# lightplay2.net
KiCad netlist of a schematic drawn in EAGLE
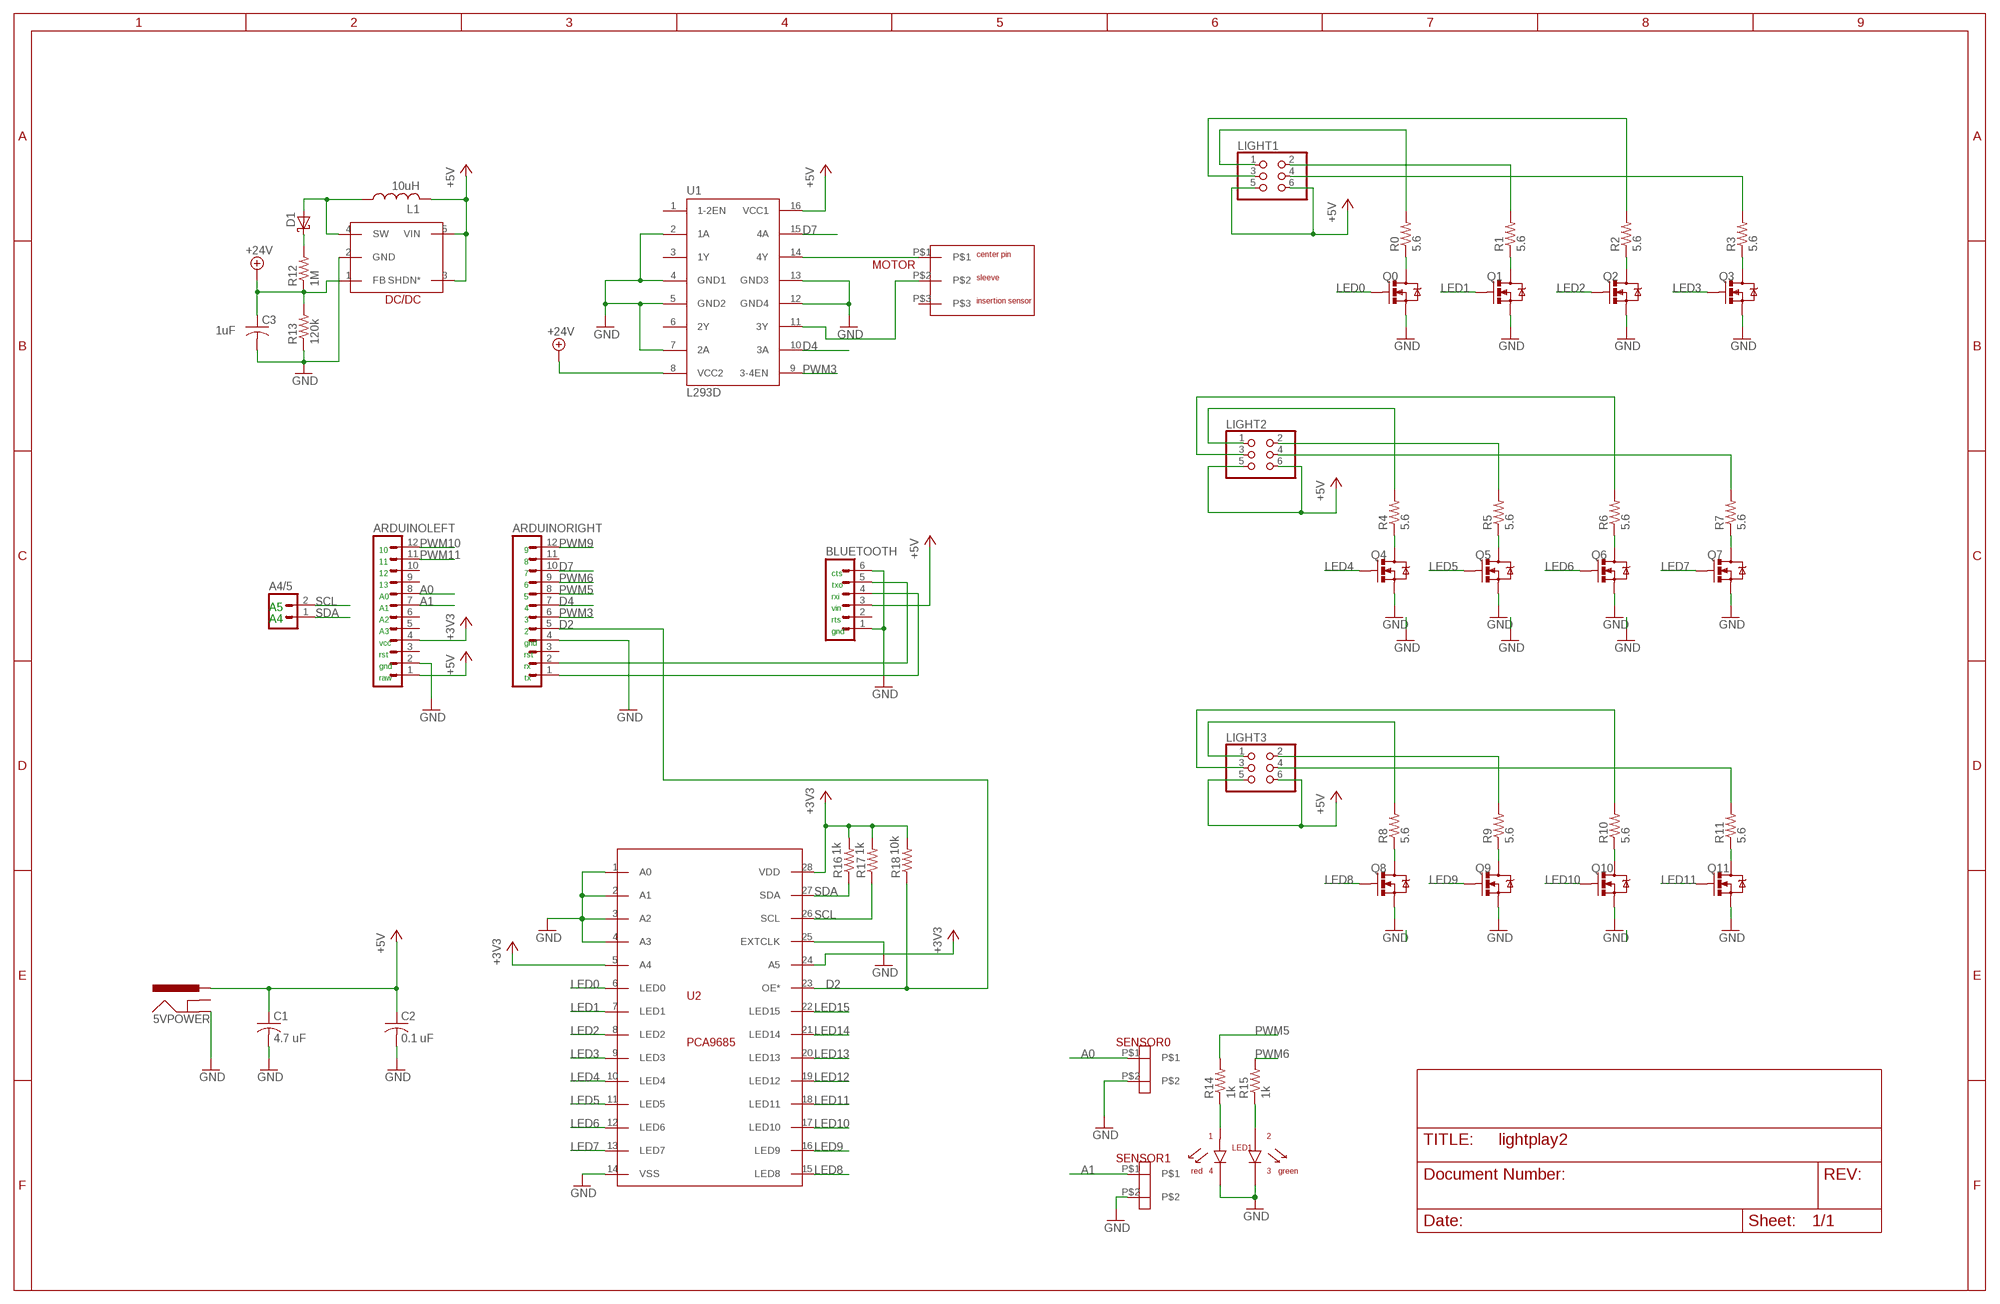
[diagram p0: schematic, sheet 1]

(export (version "E")
  (design (tool "Eeschema 10.0.6"))
  (components
    (comp (ref "5VPOWER")
      (value "POWER_JACKPTH")
      (footprint "eagle-import:POWER_JACK_PTH")
      (libsource (lib "eagle-import") (part "POWER_JACKPTH"))
    )
    (comp (ref "A4/5")
      (value "M02PTH")
      (footprint "eagle-import:1X02")
      (libsource (lib "eagle-import") (part "M02PTH"))
    )
    (comp (ref "ARDUINOLEFT")
      (value "M12PTH")
      (footprint "eagle-import:1X12")
      (libsource (lib "eagle-import") (part "M12PTH"))
    )
    (comp (ref "ARDUINORIGHT")
      (value "M12PTH")
      (footprint "eagle-import:1X12")
      (libsource (lib "eagle-import") (part "M12PTH"))
    )
    (comp (ref "BLUETOOTH")
      (value "M06SILK_FEMALE_PTH")
      (footprint "eagle-import:1X06")
      (libsource (lib "eagle-import") (part "M06SILK_FEMALE_PTH"))
    )
    (comp (ref "C1")
      (value "4.7 uF")
      (footprint "eagle-import:C1206")
      (libsource (lib "eagle-import") (part "C-USC1206"))
    )
    (comp (ref "C2")
      (value "0.1 uF")
      (footprint "eagle-import:C1206")
      (libsource (lib "eagle-import") (part "C-USC1206"))
    )
    (comp (ref "C3")
      (value "1uF")
      (footprint "eagle-import:C1206")
      (libsource (lib "eagle-import") (part "C-USC1206"))
    )
    (comp (ref "D1")
      (value "B120_SHOTTKY_DIODE")
      (footprint "eagle-import:DO214AC")
      (libsource (lib "eagle-import") (part "B120_SHOTTKY_DIODE"))
    )
    (comp (ref "DC/DC")
      (value "LT1615")
      (footprint "eagle-import:SOT23-5")
      (libsource (lib "eagle-import") (part "LT1615"))
    )
    (comp (ref "L1")
      (value "10uH")
      (footprint "eagle-import:INDUCTOR_WURTH")
      (libsource (lib "eagle-import") (part "INDUCTOR_WURTH"))
    )
    (comp (ref "LED1")
      (value "BICOLOR_LED")
      (footprint "eagle-import:BICOLOR_LED")
      (libsource (lib "eagle-import") (part "BICOLOR_LED"))
    )
    (comp (ref "LIGHT1")
      (value "PINHD-2X3")
      (footprint "eagle-import:2X03")
      (libsource (lib "eagle-import") (part "PINHD-2X3"))
    )
    (comp (ref "LIGHT2")
      (value "PINHD-2X3")
      (footprint "eagle-import:2X03")
      (libsource (lib "eagle-import") (part "PINHD-2X3"))
    )
    (comp (ref "LIGHT3")
      (value "PINHD-2X3")
      (footprint "eagle-import:2X03")
      (libsource (lib "eagle-import") (part "PINHD-2X3"))
    )
    (comp (ref "MOTOR")
      (value "PJ-075DH-SMT-TR")
      (footprint "eagle-import:PJ-075DH-SMT-TR")
      (libsource (lib "eagle-import") (part "PJ-075DH-SMT-TR"))
    )
    (comp (ref "Q0")
      (value "MOSFET-NCHANNELAO3404A")
      (footprint "eagle-import:SOT23-3")
      (libsource (lib "eagle-import") (part "MOSFET-NCHANNELAO3404A"))
    )
    (comp (ref "Q1")
      (value "MOSFET-NCHANNELAO3404A")
      (footprint "eagle-import:SOT23-3")
      (libsource (lib "eagle-import") (part "MOSFET-NCHANNELAO3404A"))
    )
    (comp (ref "Q2")
      (value "MOSFET-NCHANNELAO3404A")
      (footprint "eagle-import:SOT23-3")
      (libsource (lib "eagle-import") (part "MOSFET-NCHANNELAO3404A"))
    )
    (comp (ref "Q3")
      (value "MOSFET-NCHANNELAO3404A")
      (footprint "eagle-import:SOT23-3")
      (libsource (lib "eagle-import") (part "MOSFET-NCHANNELAO3404A"))
    )
    (comp (ref "Q4")
      (value "MOSFET-NCHANNELAO3404A")
      (footprint "eagle-import:SOT23-3")
      (libsource (lib "eagle-import") (part "MOSFET-NCHANNELAO3404A"))
    )
    (comp (ref "Q5")
      (value "MOSFET-NCHANNELAO3404A")
      (footprint "eagle-import:SOT23-3")
      (libsource (lib "eagle-import") (part "MOSFET-NCHANNELAO3404A"))
    )
    (comp (ref "Q6")
      (value "MOSFET-NCHANNELAO3404A")
      (footprint "eagle-import:SOT23-3")
      (libsource (lib "eagle-import") (part "MOSFET-NCHANNELAO3404A"))
    )
    (comp (ref "Q7")
      (value "MOSFET-NCHANNELAO3404A")
      (footprint "eagle-import:SOT23-3")
      (libsource (lib "eagle-import") (part "MOSFET-NCHANNELAO3404A"))
    )
    (comp (ref "Q8")
      (value "MOSFET-NCHANNELAO3404A")
      (footprint "eagle-import:SOT23-3")
      (libsource (lib "eagle-import") (part "MOSFET-NCHANNELAO3404A"))
    )
    (comp (ref "Q9")
      (value "MOSFET-NCHANNELAO3404A")
      (footprint "eagle-import:SOT23-3")
      (libsource (lib "eagle-import") (part "MOSFET-NCHANNELAO3404A"))
    )
    (comp (ref "Q10")
      (value "MOSFET-NCHANNELAO3404A")
      (footprint "eagle-import:SOT23-3")
      (libsource (lib "eagle-import") (part "MOSFET-NCHANNELAO3404A"))
    )
    (comp (ref "Q11")
      (value "MOSFET-NCHANNELAO3404A")
      (footprint "eagle-import:SOT23-3")
      (libsource (lib "eagle-import") (part "MOSFET-NCHANNELAO3404A"))
    )
    (comp (ref "R0")
      (value "5.6")
      (footprint "eagle-import:0207_10")
      (libsource (lib "eagle-import") (part "R-US_0207/10"))
    )
    (comp (ref "R1")
      (value "5.6")
      (footprint "eagle-import:0207_10")
      (libsource (lib "eagle-import") (part "R-US_0207/10"))
    )
    (comp (ref "R2")
      (value "5.6")
      (footprint "eagle-import:0207_10")
      (libsource (lib "eagle-import") (part "R-US_0207/10"))
    )
    (comp (ref "R3")
      (value "5.6")
      (footprint "eagle-import:0207_10")
      (libsource (lib "eagle-import") (part "R-US_0207/10"))
    )
    (comp (ref "R4")
      (value "5.6")
      (footprint "eagle-import:0207_10")
      (libsource (lib "eagle-import") (part "R-US_0207/10"))
    )
    (comp (ref "R5")
      (value "5.6")
      (footprint "eagle-import:0207_10")
      (libsource (lib "eagle-import") (part "R-US_0207/10"))
    )
    (comp (ref "R6")
      (value "5.6")
      (footprint "eagle-import:0207_10")
      (libsource (lib "eagle-import") (part "R-US_0207/10"))
    )
    (comp (ref "R7")
      (value "5.6")
      (footprint "eagle-import:0207_10")
      (libsource (lib "eagle-import") (part "R-US_0207/10"))
    )
    (comp (ref "R8")
      (value "5.6")
      (footprint "eagle-import:0207_10")
      (libsource (lib "eagle-import") (part "R-US_0207/10"))
    )
    (comp (ref "R9")
      (value "5.6")
      (footprint "eagle-import:0207_10")
      (libsource (lib "eagle-import") (part "R-US_0207/10"))
    )
    (comp (ref "R10")
      (value "5.6")
      (footprint "eagle-import:0207_10")
      (libsource (lib "eagle-import") (part "R-US_0207/10"))
    )
    (comp (ref "R11")
      (value "5.6")
      (footprint "eagle-import:0207_10")
      (libsource (lib "eagle-import") (part "R-US_0207/10"))
    )
    (comp (ref "R12")
      (value "1M")
      (footprint "eagle-import:R0805")
      (libsource (lib "eagle-import") (part "R-US_R0805"))
    )
    (comp (ref "R13")
      (value "120k")
      (footprint "eagle-import:R0805")
      (libsource (lib "eagle-import") (part "R-US_R0805"))
    )
    (comp (ref "R14")
      (value "1k")
      (footprint "eagle-import:R0805")
      (libsource (lib "eagle-import") (part "R-US_R0805"))
    )
    (comp (ref "R15")
      (value "1k")
      (footprint "eagle-import:R0805")
      (libsource (lib "eagle-import") (part "R-US_R0805"))
    )
    (comp (ref "R16")
      (value "1k")
      (footprint "eagle-import:R0805")
      (libsource (lib "eagle-import") (part "R-US_R0805"))
    )
    (comp (ref "R17")
      (value "1k")
      (footprint "eagle-import:R0805")
      (libsource (lib "eagle-import") (part "R-US_R0805"))
    )
    (comp (ref "R18")
      (value "10k")
      (footprint "eagle-import:R0805")
      (libsource (lib "eagle-import") (part "R-US_R0805"))
    )
    (comp (ref "SENSOR0")
      (value "3.5MM_2PIN_SCREWTERMINAL_SPARKFUN")
      (footprint "eagle-import:1X02_3.5_SCREWTERM")
      (libsource (lib "eagle-import") (part "3.5MM_2PIN_SCREWTERMINAL_SPARKFUN"))
    )
    (comp (ref "SENSOR1")
      (value "3.5MM_2PIN_SCREWTERMINAL_SPARKFUN")
      (footprint "eagle-import:1X02_3.5_SCREWTERM")
      (libsource (lib "eagle-import") (part "3.5MM_2PIN_SCREWTERMINAL_SPARKFUN"))
    )
    (comp (ref "U1")
      (value "L293D")
      (footprint "eagle-import:DIL16")
      (libsource (lib "eagle-import") (part "L293D"))
    )
    (comp (ref "U2")
      (value "PCA9685")
      (footprint "eagle-import:TSSOP28")
      (libsource (lib "eagle-import") (part "PCA9685"))
    )
  )
  (nets
    (net (code "1") (name "+3V3") (class "Default")
      (node (ref "ARDUINOLEFT") (pin "4") (pinfunction "4_4") (pintype "passive"))
      (node (ref "R16") (pin "2") (pinfunction "2_2") (pintype "passive"))
      (node (ref "R17") (pin "2") (pinfunction "2_2") (pintype "passive"))
      (node (ref "R18") (pin "2") (pinfunction "2_2") (pintype "passive"))
      (node (ref "U2") (pin "24") (pinfunction "A5_24") (pintype "bidirectional"))
      (node (ref "U2") (pin "28") (pinfunction "VDD_28") (pintype "bidirectional"))
      (node (ref "U2") (pin "5") (pinfunction "A4_5") (pintype "bidirectional"))
    )
    (net (code "2") (name "+5V") (class "Default")
      (node (ref "5VPOWER") (pin "PWR") (pinfunction "PWR_PWR") (pintype "bidirectional"))
      (node (ref "ARDUINOLEFT") (pin "1") (pinfunction "1_1") (pintype "passive"))
      (node (ref "BLUETOOTH") (pin "3") (pinfunction "3_3") (pintype "passive"))
      (node (ref "C1") (pin "1") (pinfunction "1_1") (pintype "passive"))
      (node (ref "C2") (pin "1") (pinfunction "1_1") (pintype "passive"))
      (node (ref "DC/DC") (pin "3") (pinfunction "SHDN*_3") (pintype "bidirectional"))
      (node (ref "DC/DC") (pin "5") (pinfunction "VIN_5") (pintype "bidirectional"))
      (node (ref "L1") (pin "P$2") (pinfunction "2_P$2") (pintype "passive"))
      (node (ref "LIGHT1") (pin "5") (pinfunction "5_5") (pintype "passive"))
      (node (ref "LIGHT1") (pin "6") (pinfunction "6_6") (pintype "passive"))
      (node (ref "LIGHT2") (pin "5") (pinfunction "5_5") (pintype "passive"))
      (node (ref "LIGHT2") (pin "6") (pinfunction "6_6") (pintype "passive"))
      (node (ref "LIGHT3") (pin "5") (pinfunction "5_5") (pintype "passive"))
      (node (ref "LIGHT3") (pin "6") (pinfunction "6_6") (pintype "passive"))
      (node (ref "U1") (pin "16") (pinfunction "VCC1_16") (pintype "power_in"))
    )
    (net (code "3") (name "+24V") (class "Default")
      (node (ref "C3") (pin "1") (pinfunction "1_1") (pintype "passive"))
      (node (ref "DC/DC") (pin "1") (pinfunction "FB_1") (pintype "bidirectional"))
      (node (ref "R12") (pin "1") (pinfunction "1_1") (pintype "passive"))
      (node (ref "R13") (pin "2") (pinfunction "2_2") (pintype "passive"))
      (node (ref "U1") (pin "8") (pinfunction "VCC2_8") (pintype "power_in"))
    )
    (net (code "4") (name "/A0") (class "Default")
      (node (ref "ARDUINOLEFT") (pin "8") (pinfunction "8_8") (pintype "passive"))
      (node (ref "SENSOR0") (pin "P$1") (pinfunction "P$1_P$1") (pintype "bidirectional"))
    )
    (net (code "5") (name "/A1") (class "Default")
      (node (ref "ARDUINOLEFT") (pin "7") (pinfunction "7_7") (pintype "passive"))
      (node (ref "SENSOR1") (pin "P$1") (pinfunction "P$1_P$1") (pintype "bidirectional"))
    )
    (net (code "6") (name "/D2") (class "Default")
      (node (ref "ARDUINORIGHT") (pin "5") (pinfunction "5_5") (pintype "passive"))
      (node (ref "R18") (pin "1") (pinfunction "1_1") (pintype "passive"))
      (node (ref "U2") (pin "23") (pinfunction "OE*_23") (pintype "bidirectional"))
    )
    (net (code "7") (name "/D4") (class "Default")
      (node (ref "ARDUINORIGHT") (pin "7") (pinfunction "7_7") (pintype "passive"))
      (node (ref "U1") (pin "10") (pinfunction "3A_10") (pintype "input"))
    )
    (net (code "8") (name "/D7") (class "Default")
      (node (ref "ARDUINORIGHT") (pin "10") (pinfunction "10_10") (pintype "passive"))
      (node (ref "U1") (pin "15") (pinfunction "4A_15") (pintype "input"))
    )
    (net (code "9") (name "/LED0") (class "Default")
      (node (ref "Q0") (pin "1") (pinfunction "G_1") (pintype "passive"))
      (node (ref "U2") (pin "6") (pinfunction "LED0_6") (pintype "bidirectional"))
    )
    (net (code "10") (name "/LED1") (class "Default")
      (node (ref "Q1") (pin "1") (pinfunction "G_1") (pintype "passive"))
      (node (ref "U2") (pin "7") (pinfunction "LED1_7") (pintype "bidirectional"))
    )
    (net (code "11") (name "/LED2") (class "Default")
      (node (ref "Q2") (pin "1") (pinfunction "G_1") (pintype "passive"))
      (node (ref "U2") (pin "8") (pinfunction "LED2_8") (pintype "bidirectional"))
    )
    (net (code "12") (name "/LED3") (class "Default")
      (node (ref "Q3") (pin "1") (pinfunction "G_1") (pintype "passive"))
      (node (ref "U2") (pin "9") (pinfunction "LED3_9") (pintype "bidirectional"))
    )
    (net (code "13") (name "/LED4") (class "Default")
      (node (ref "Q4") (pin "1") (pinfunction "G_1") (pintype "passive"))
      (node (ref "U2") (pin "10") (pinfunction "LED4_10") (pintype "bidirectional"))
    )
    (net (code "14") (name "/LED5") (class "Default")
      (node (ref "Q5") (pin "1") (pinfunction "G_1") (pintype "passive"))
      (node (ref "U2") (pin "11") (pinfunction "LED5_11") (pintype "bidirectional"))
    )
    (net (code "15") (name "/LED6") (class "Default")
      (node (ref "Q6") (pin "1") (pinfunction "G_1") (pintype "passive"))
      (node (ref "U2") (pin "12") (pinfunction "LED6_12") (pintype "bidirectional"))
    )
    (net (code "16") (name "/LED7") (class "Default")
      (node (ref "Q7") (pin "1") (pinfunction "G_1") (pintype "passive"))
      (node (ref "U2") (pin "13") (pinfunction "LED7_13") (pintype "bidirectional"))
    )
    (net (code "17") (name "/LED8") (class "Default")
      (node (ref "Q8") (pin "1") (pinfunction "G_1") (pintype "passive"))
      (node (ref "U2") (pin "15") (pinfunction "LED8_15") (pintype "bidirectional"))
    )
    (net (code "18") (name "/LED9") (class "Default")
      (node (ref "Q9") (pin "1") (pinfunction "G_1") (pintype "passive"))
      (node (ref "U2") (pin "16") (pinfunction "LED9_16") (pintype "bidirectional"))
    )
    (net (code "19") (name "/LED10") (class "Default")
      (node (ref "Q10") (pin "1") (pinfunction "G_1") (pintype "passive"))
      (node (ref "U2") (pin "17") (pinfunction "LED10_17") (pintype "bidirectional"))
    )
    (net (code "20") (name "/LED11") (class "Default")
      (node (ref "Q11") (pin "1") (pinfunction "G_1") (pintype "passive"))
      (node (ref "U2") (pin "18") (pinfunction "LED11_18") (pintype "bidirectional"))
    )
    (net (code "21") (name "/LED12") (class "Default")
      (node (ref "U2") (pin "19") (pinfunction "LED12_19") (pintype "bidirectional"))
    )
    (net (code "22") (name "/LED13") (class "Default")
      (node (ref "U2") (pin "20") (pinfunction "LED13_20") (pintype "bidirectional"))
    )
    (net (code "23") (name "/LED14") (class "Default")
      (node (ref "U2") (pin "21") (pinfunction "LED14_21") (pintype "bidirectional"))
    )
    (net (code "24") (name "/LED15") (class "Default")
      (node (ref "U2") (pin "22") (pinfunction "LED15_22") (pintype "bidirectional"))
    )
    (net (code "25") (name "/PWM3") (class "Default")
      (node (ref "ARDUINORIGHT") (pin "6") (pinfunction "6_6") (pintype "passive"))
      (node (ref "U1") (pin "9") (pinfunction "3-4EN_9") (pintype "input"))
    )
    (net (code "26") (name "/PWM5") (class "Default")
      (node (ref "ARDUINORIGHT") (pin "8") (pinfunction "8_8") (pintype "passive"))
      (node (ref "R14") (pin "2") (pinfunction "2_2") (pintype "passive"))
    )
    (net (code "27") (name "/PWM6") (class "Default")
      (node (ref "ARDUINORIGHT") (pin "9") (pinfunction "9_9") (pintype "passive"))
      (node (ref "R15") (pin "2") (pinfunction "2_2") (pintype "passive"))
    )
    (net (code "28") (name "/PWM9") (class "Default")
      (node (ref "ARDUINORIGHT") (pin "12") (pinfunction "12_12") (pintype "passive"))
    )
    (net (code "29") (name "/PWM10") (class "Default")
      (node (ref "ARDUINOLEFT") (pin "12") (pinfunction "12_12") (pintype "passive"))
    )
    (net (code "30") (name "/PWM11") (class "Default")
      (node (ref "ARDUINOLEFT") (pin "11") (pinfunction "11_11") (pintype "passive"))
    )
    (net (code "31") (name "/SCL") (class "Default")
      (node (ref "A4/5") (pin "2") (pinfunction "2_2") (pintype "passive"))
      (node (ref "R17") (pin "1") (pinfunction "1_1") (pintype "passive"))
      (node (ref "U2") (pin "26") (pinfunction "SCL_26") (pintype "bidirectional"))
    )
    (net (code "32") (name "/SDA") (class "Default")
      (node (ref "A4/5") (pin "1") (pinfunction "1_1") (pintype "passive"))
      (node (ref "R16") (pin "1") (pinfunction "1_1") (pintype "passive"))
      (node (ref "U2") (pin "27") (pinfunction "SDA_27") (pintype "bidirectional"))
    )
    (net (code "33") (name "GND") (class "Default")
      (node (ref "5VPOWER") (pin "GND") (pinfunction "GND_GND") (pintype "bidirectional"))
      (node (ref "ARDUINOLEFT") (pin "2") (pinfunction "2_2") (pintype "passive"))
      (node (ref "ARDUINORIGHT") (pin "4") (pinfunction "4_4") (pintype "passive"))
      (node (ref "BLUETOOTH") (pin "1") (pinfunction "1_1") (pintype "passive"))
      (node (ref "BLUETOOTH") (pin "6") (pinfunction "6_6") (pintype "passive"))
      (node (ref "C1") (pin "2") (pinfunction "2_2") (pintype "passive"))
      (node (ref "C2") (pin "2") (pinfunction "2_2") (pintype "passive"))
      (node (ref "C3") (pin "2") (pinfunction "2_2") (pintype "passive"))
      (node (ref "DC/DC") (pin "2") (pinfunction "GND_2") (pintype "bidirectional"))
      (node (ref "Q0") (pin "2") (pinfunction "S_2") (pintype "passive"))
      (node (ref "Q1") (pin "2") (pinfunction "S_2") (pintype "passive"))
      (node (ref "Q10") (pin "2") (pinfunction "S_2") (pintype "passive"))
      (node (ref "Q11") (pin "2") (pinfunction "S_2") (pintype "passive"))
      (node (ref "Q2") (pin "2") (pinfunction "S_2") (pintype "passive"))
      (node (ref "Q3") (pin "2") (pinfunction "S_2") (pintype "passive"))
      (node (ref "Q4") (pin "2") (pinfunction "S_2") (pintype "passive"))
      (node (ref "Q5") (pin "2") (pinfunction "S_2") (pintype "passive"))
      (node (ref "Q6") (pin "2") (pinfunction "S_2") (pintype "passive"))
      (node (ref "Q7") (pin "2") (pinfunction "S_2") (pintype "passive"))
      (node (ref "Q8") (pin "2") (pinfunction "S_2") (pintype "passive"))
      (node (ref "Q9") (pin "2") (pinfunction "S_2") (pintype "passive"))
      (node (ref "R13") (pin "1") (pinfunction "1_1") (pintype "passive"))
      (node (ref "SENSOR0") (pin "P$2") (pinfunction "P$2_P$2") (pintype "bidirectional"))
      (node (ref "SENSOR1") (pin "P$2") (pinfunction "P$2_P$2") (pintype "bidirectional"))
      (node (ref "U1") (pin "12") (pinfunction "GND4_12") (pintype "power_in"))
      (node (ref "U1") (pin "13") (pinfunction "GND3_13") (pintype "power_in"))
      (node (ref "U1") (pin "2") (pinfunction "1A_2") (pintype "input"))
      (node (ref "U1") (pin "4") (pinfunction "GND1_4") (pintype "power_in"))
      (node (ref "U1") (pin "5") (pinfunction "GND2_5") (pintype "power_in"))
      (node (ref "U1") (pin "7") (pinfunction "2A_7") (pintype "input"))
      (node (ref "U2") (pin "1") (pinfunction "A0_1") (pintype "bidirectional"))
      (node (ref "U2") (pin "14") (pinfunction "VSS_14") (pintype "bidirectional"))
      (node (ref "U2") (pin "2") (pinfunction "A1_2") (pintype "bidirectional"))
      (node (ref "U2") (pin "25") (pinfunction "EXTCLK_25") (pintype "bidirectional"))
      (node (ref "U2") (pin "3") (pinfunction "A2_3") (pintype "bidirectional"))
      (node (ref "U2") (pin "4") (pinfunction "A3_4") (pintype "bidirectional"))
    )
    (net (code "34") (name "Net-(ARDUINORIGHT-Pad1)") (class "Default")
      (node (ref "ARDUINORIGHT") (pin "1") (pinfunction "1_1") (pintype "passive"))
      (node (ref "BLUETOOTH") (pin "4") (pinfunction "4_4") (pintype "passive"))
    )
    (net (code "35") (name "Net-(ARDUINORIGHT-Pad2)") (class "Default")
      (node (ref "ARDUINORIGHT") (pin "2") (pinfunction "2_2") (pintype "passive"))
      (node (ref "BLUETOOTH") (pin "5") (pinfunction "5_5") (pintype "passive"))
    )
    (net (code "36") (name "Net-(D1-PadC)") (class "Default")
      (node (ref "D1") (pin "C") (pinfunction "C_C") (pintype "passive"))
      (node (ref "R12") (pin "2") (pinfunction "2_2") (pintype "passive"))
    )
    (net (code "37") (name "Net-(DC/DC-SW)") (class "Default")
      (node (ref "D1") (pin "A") (pinfunction "A_A") (pintype "passive"))
      (node (ref "DC/DC") (pin "4") (pinfunction "SW_4") (pintype "bidirectional"))
      (node (ref "L1") (pin "P$1") (pinfunction "1_P$1") (pintype "passive"))
    )
    (net (code "38") (name "Net-(LED1-PadP$1)") (class "Default")
      (node (ref "LED1") (pin "P$1") (pinfunction "P$1_P$1") (pintype "bidirectional"))
      (node (ref "R14") (pin "1") (pinfunction "1_1") (pintype "passive"))
    )
    (net (code "39") (name "Net-(LED1-PadP$2)") (class "Default")
      (node (ref "LED1") (pin "P$2") (pinfunction "P$2_P$2") (pintype "bidirectional"))
      (node (ref "R15") (pin "1") (pinfunction "1_1") (pintype "passive"))
    )
    (net (code "40") (name "Net-(LIGHT1-Pad1)") (class "Default")
      (node (ref "LIGHT1") (pin "1") (pinfunction "1_1") (pintype "passive"))
      (node (ref "R0") (pin "2") (pinfunction "2_2") (pintype "passive"))
    )
    (net (code "41") (name "Net-(LIGHT1-Pad2)") (class "Default")
      (node (ref "LIGHT1") (pin "2") (pinfunction "2_2") (pintype "passive"))
      (node (ref "R1") (pin "2") (pinfunction "2_2") (pintype "passive"))
    )
    (net (code "42") (name "Net-(LIGHT1-Pad3)") (class "Default")
      (node (ref "LIGHT1") (pin "3") (pinfunction "3_3") (pintype "passive"))
      (node (ref "R2") (pin "2") (pinfunction "2_2") (pintype "passive"))
    )
    (net (code "43") (name "Net-(LIGHT1-Pad4)") (class "Default")
      (node (ref "LIGHT1") (pin "4") (pinfunction "4_4") (pintype "passive"))
      (node (ref "R3") (pin "2") (pinfunction "2_2") (pintype "passive"))
    )
    (net (code "44") (name "Net-(LIGHT2-Pad1)") (class "Default")
      (node (ref "LIGHT2") (pin "1") (pinfunction "1_1") (pintype "passive"))
      (node (ref "R4") (pin "2") (pinfunction "2_2") (pintype "passive"))
    )
    (net (code "45") (name "Net-(LIGHT2-Pad2)") (class "Default")
      (node (ref "LIGHT2") (pin "2") (pinfunction "2_2") (pintype "passive"))
      (node (ref "R5") (pin "2") (pinfunction "2_2") (pintype "passive"))
    )
    (net (code "46") (name "Net-(LIGHT2-Pad3)") (class "Default")
      (node (ref "LIGHT2") (pin "3") (pinfunction "3_3") (pintype "passive"))
      (node (ref "R6") (pin "2") (pinfunction "2_2") (pintype "passive"))
    )
    (net (code "47") (name "Net-(LIGHT2-Pad4)") (class "Default")
      (node (ref "LIGHT2") (pin "4") (pinfunction "4_4") (pintype "passive"))
      (node (ref "R7") (pin "2") (pinfunction "2_2") (pintype "passive"))
    )
    (net (code "48") (name "Net-(LIGHT3-Pad1)") (class "Default")
      (node (ref "LIGHT3") (pin "1") (pinfunction "1_1") (pintype "passive"))
      (node (ref "R8") (pin "2") (pinfunction "2_2") (pintype "passive"))
    )
    (net (code "49") (name "Net-(LIGHT3-Pad2)") (class "Default")
      (node (ref "LIGHT3") (pin "2") (pinfunction "2_2") (pintype "passive"))
      (node (ref "R9") (pin "2") (pinfunction "2_2") (pintype "passive"))
    )
    (net (code "50") (name "Net-(LIGHT3-Pad3)") (class "Default")
      (node (ref "LIGHT3") (pin "3") (pinfunction "3_3") (pintype "passive"))
      (node (ref "R10") (pin "2") (pinfunction "2_2") (pintype "passive"))
    )
    (net (code "51") (name "Net-(LIGHT3-Pad4)") (class "Default")
      (node (ref "LIGHT3") (pin "4") (pinfunction "4_4") (pintype "passive"))
      (node (ref "R11") (pin "2") (pinfunction "2_2") (pintype "passive"))
    )
    (net (code "52") (name "Net-(Q0-D)") (class "Default")
      (node (ref "Q0") (pin "3") (pinfunction "D_3") (pintype "passive"))
      (node (ref "R0") (pin "1") (pinfunction "1_1") (pintype "passive"))
    )
    (net (code "53") (name "Net-(Q1-D)") (class "Default")
      (node (ref "Q1") (pin "3") (pinfunction "D_3") (pintype "passive"))
      (node (ref "R1") (pin "1") (pinfunction "1_1") (pintype "passive"))
    )
    (net (code "54") (name "Net-(Q2-D)") (class "Default")
      (node (ref "Q2") (pin "3") (pinfunction "D_3") (pintype "passive"))
      (node (ref "R2") (pin "1") (pinfunction "1_1") (pintype "passive"))
    )
    (net (code "55") (name "Net-(Q3-D)") (class "Default")
      (node (ref "Q3") (pin "3") (pinfunction "D_3") (pintype "passive"))
      (node (ref "R3") (pin "1") (pinfunction "1_1") (pintype "passive"))
    )
    (net (code "56") (name "Net-(Q4-D)") (class "Default")
      (node (ref "Q4") (pin "3") (pinfunction "D_3") (pintype "passive"))
      (node (ref "R4") (pin "1") (pinfunction "1_1") (pintype "passive"))
    )
    (net (code "57") (name "Net-(Q5-D)") (class "Default")
      (node (ref "Q5") (pin "3") (pinfunction "D_3") (pintype "passive"))
      (node (ref "R5") (pin "1") (pinfunction "1_1") (pintype "passive"))
    )
    (net (code "58") (name "Net-(Q6-D)") (class "Default")
      (node (ref "Q6") (pin "3") (pinfunction "D_3") (pintype "passive"))
      (node (ref "R6") (pin "1") (pinfunction "1_1") (pintype "passive"))
    )
    (net (code "59") (name "Net-(Q7-D)") (class "Default")
      (node (ref "Q7") (pin "3") (pinfunction "D_3") (pintype "passive"))
      (node (ref "R7") (pin "1") (pinfunction "1_1") (pintype "passive"))
    )
    (net (code "60") (name "Net-(Q8-D)") (class "Default")
      (node (ref "Q8") (pin "3") (pinfunction "D_3") (pintype "passive"))
      (node (ref "R8") (pin "1") (pinfunction "1_1") (pintype "passive"))
    )
    (net (code "61") (name "Net-(Q9-D)") (class "Default")
      (node (ref "Q9") (pin "3") (pinfunction "D_3") (pintype "passive"))
      (node (ref "R9") (pin "1") (pinfunction "1_1") (pintype "passive"))
    )
    (net (code "62") (name "Net-(Q10-D)") (class "Default")
      (node (ref "Q10") (pin "3") (pinfunction "D_3") (pintype "passive"))
      (node (ref "R10") (pin "1") (pinfunction "1_1") (pintype "passive"))
    )
    (net (code "63") (name "Net-(Q11-D)") (class "Default")
      (node (ref "Q11") (pin "3") (pinfunction "D_3") (pintype "passive"))
      (node (ref "R11") (pin "1") (pinfunction "1_1") (pintype "passive"))
    )
    (net (code "64") (name "Net-(U1-3Y)") (class "Default")
      (node (ref "MOTOR") (pin "P$2") (pinfunction "P$2_P$2") (pintype "bidirectional"))
      (node (ref "U1") (pin "11") (pinfunction "3Y_11") (pintype "output"))
    )
    (net (code "65") (name "Net-(U1-4Y)") (class "Default")
      (node (ref "MOTOR") (pin "P$1") (pinfunction "P$1_P$1") (pintype "bidirectional"))
      (node (ref "U1") (pin "14") (pinfunction "4Y_14") (pintype "output"))
    )
    (net (code "66") (name "unconnected-(5VPOWER-PadGNDBREAK)") (class "Default")
      (node (ref "5VPOWER") (pin "GNDBREAK") (pinfunction "GNDBREAK_GNDBREAK") (pintype "bidirectional"))
    )
    (net (code "67") (name "unconnected-(ARDUINOLEFT-Pad3)") (class "Default")
      (node (ref "ARDUINOLEFT") (pin "3") (pinfunction "3_3") (pintype "passive"))
    )
    (net (code "68") (name "unconnected-(ARDUINOLEFT-Pad5)") (class "Default")
      (node (ref "ARDUINOLEFT") (pin "5") (pinfunction "5_5") (pintype "passive"))
    )
    (net (code "69") (name "unconnected-(ARDUINOLEFT-Pad6)") (class "Default")
      (node (ref "ARDUINOLEFT") (pin "6") (pinfunction "6_6") (pintype "passive"))
    )
    (net (code "70") (name "unconnected-(ARDUINOLEFT-Pad9)") (class "Default")
      (node (ref "ARDUINOLEFT") (pin "9") (pinfunction "9_9") (pintype "passive"))
    )
    (net (code "71") (name "unconnected-(ARDUINOLEFT-Pad10)") (class "Default")
      (node (ref "ARDUINOLEFT") (pin "10") (pinfunction "10_10") (pintype "passive"))
    )
    (net (code "72") (name "unconnected-(ARDUINORIGHT-Pad3)") (class "Default")
      (node (ref "ARDUINORIGHT") (pin "3") (pinfunction "3_3") (pintype "passive"))
    )
    (net (code "73") (name "unconnected-(ARDUINORIGHT-Pad11)") (class "Default")
      (node (ref "ARDUINORIGHT") (pin "11") (pinfunction "11_11") (pintype "passive"))
    )
    (net (code "74") (name "unconnected-(BLUETOOTH-Pad2)") (class "Default")
      (node (ref "BLUETOOTH") (pin "2") (pinfunction "2_2") (pintype "passive"))
    )
    (net (code "75") (name "unconnected-(LED1-PadP$3)") (class "Default")
      (node (ref "LED1") (pin "P$3") (pinfunction "P$3_P$3") (pintype "bidirectional"))
    )
    (net (code "76") (name "unconnected-(LED1-PadP$4)") (class "Default")
      (node (ref "LED1") (pin "P$4") (pinfunction "P$4_P$4") (pintype "bidirectional"))
    )
    (net (code "77") (name "unconnected-(MOTOR-PadP$3)") (class "Default")
      (node (ref "MOTOR") (pin "P$3") (pinfunction "P$3_P$3") (pintype "bidirectional"))
    )
    (net (code "78") (name "unconnected-(U1-1-2EN-Pad1)") (class "Default")
      (node (ref "U1") (pin "1") (pinfunction "1-2EN_1") (pintype "input"))
    )
    (net (code "79") (name "unconnected-(U1-1Y-Pad3)") (class "Default")
      (node (ref "U1") (pin "3") (pinfunction "1Y_3") (pintype "output"))
    )
    (net (code "80") (name "unconnected-(U1-2Y-Pad6)") (class "Default")
      (node (ref "U1") (pin "6") (pinfunction "2Y_6") (pintype "output"))
    )
  )
)
